# PWM_Controller_Half_Bridge.net
KiCad netlist of a schematic drawn in Altium Designer
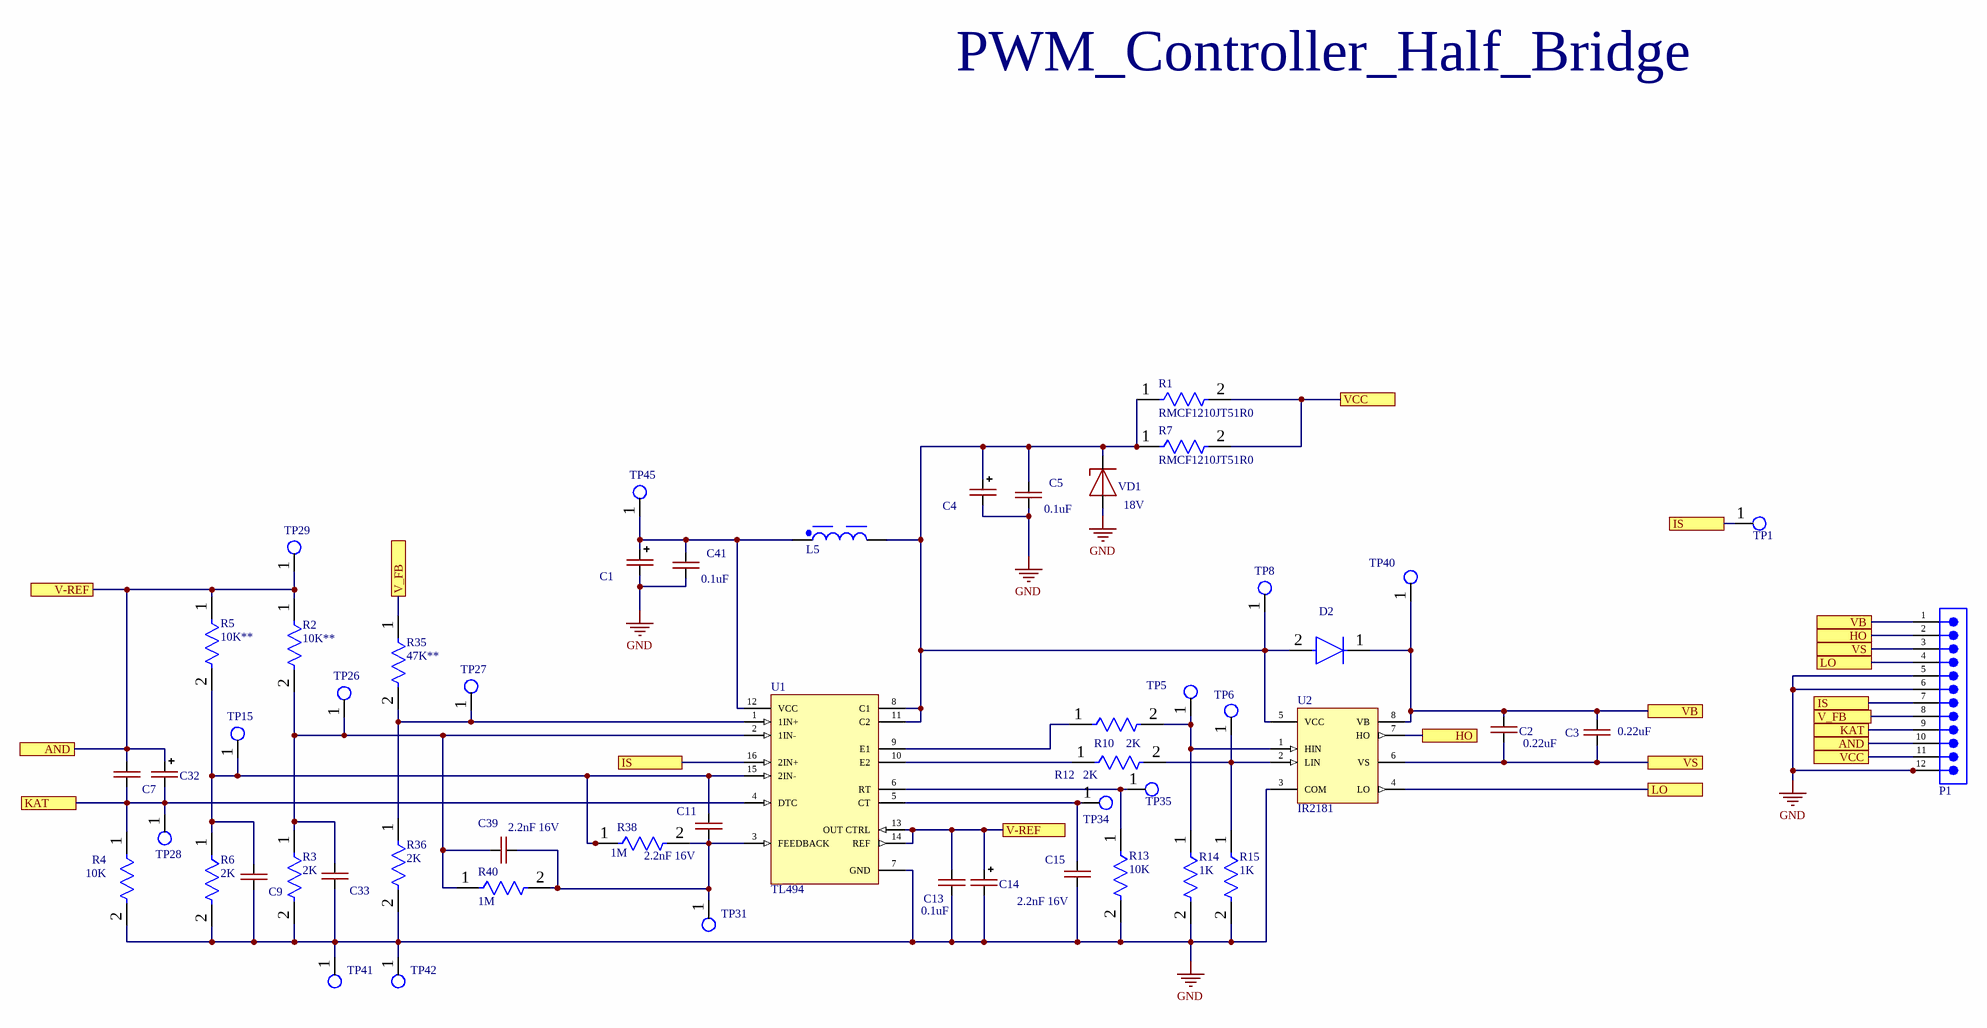
[diagram p0: PWM_Controller_Half_Bridge.SchDoc]

(export (version "E")
  (design (tool "Eeschema 10.0.6"))
  (components
    (comp (ref "C1")
      (value "CAP-POLAR")
      (footprint "SIZE_EEE")
      (libsource (lib "PASSIVE_COMPONENTS") (part "CAP-POLAR"))
    )
    (comp (ref "C2")
      (value "0.22uF")
      (footprint "FP-C1210X475K5RACTU-IPC_C")
      (libsource (lib "PASSIVE_COMPONENTS") (part "CAP_1210"))
    )
    (comp (ref "C3")
      (value "0.22uF")
      (footprint "FP-C1210X475K5RACTU-IPC_C")
      (libsource (lib "PASSIVE_COMPONENTS") (part "CAP_1210"))
    )
    (comp (ref "C4")
      (value "CAP-POLAR")
      (footprint "SIZE_EEE")
      (libsource (lib "PASSIVE_COMPONENTS") (part "CAP-POLAR"))
    )
    (comp (ref "C5")
      (value "0.1uF")
      (footprint "CAP-0805")
      (libsource (lib "PASSIVE_COMPONENTS") (part "CAP-NON-POLAR"))
    )
    (comp (ref "C7")
      (value "CAP-NON-POLAR")
      (footprint "CAP-0805")
      (libsource (lib "PASSIVE_COMPONENTS") (part "CAP-NON-POLAR"))
    )
    (comp (ref "C9")
      (value "CAP-NON-POLAR")
      (footprint "CAP-0805")
      (libsource (lib "PASSIVE_COMPONENTS") (part "CAP-NON-POLAR"))
    )
    (comp (ref "C11")
      (value "2.2nF 16V")
      (footprint "CAP-0805")
      (libsource (lib "PASSIVE_COMPONENTS") (part "CAP-NON-POLAR"))
    )
    (comp (ref "C13")
      (value "0.1uF")
      (footprint "CAP-0805")
      (libsource (lib "PASSIVE_COMPONENTS") (part "CAP-NON-POLAR"))
    )
    (comp (ref "C14")
      (value "CAP-POLAR")
      (footprint "SIZE_EEE")
      (libsource (lib "PASSIVE_COMPONENTS") (part "CAP-POLAR"))
    )
    (comp (ref "C15")
      (value "2.2nF 16V")
      (footprint "CAP-0805")
      (libsource (lib "PASSIVE_COMPONENTS") (part "CAP-NON-POLAR"))
    )
    (comp (ref "C32")
      (value "CAP-POLAR")
      (footprint "CAP-TAN-D")
      (libsource (lib "PASSIVE_COMPONENTS") (part "CAP-POLAR"))
    )
    (comp (ref "C33")
      (value "CAP-NON-POLAR")
      (footprint "CAP-0805")
      (libsource (lib "PASSIVE_COMPONENTS") (part "CAP-NON-POLAR"))
    )
    (comp (ref "C39")
      (value "2.2nF 16V")
      (footprint "CAP-0805")
      (libsource (lib "PASSIVE_COMPONENTS") (part "CAP-NON-POLAR"))
    )
    (comp (ref "C41")
      (value "0.1uF")
      (footprint "CAP-0805")
      (libsource (lib "PASSIVE_COMPONENTS") (part "CAP-NON-POLAR"))
    )
    (comp (ref "D2") (value "US1G") (footprint "DO-214AA") (libsource (lib "Diodes") (part "US1G")))
    (comp (ref "L5")
      (value "47µH, 1.17A")
      (footprint "WE-PD2_7850")
      (description "WE-PD2 SMT Power Inductor, size 7850, 47µH, 1.17A, 0.18Ω")
      (fields
        (field (name "MANUFACTURER PART NUMBER") "744775147")
        (field (name "MANUFACTURER") "Wurth Elektronik")
      )
      (libsource (lib "WE-PD2 (rev22d)") (part "744775147"))
    )
    (comp (ref "P1")
      (value "61301211021")
      (footprint "61301211021")
      (description "WR-PHD Pin Header, THT, Angled, pitch 2.54mm, 1 Row, 12P")
      (fields (field (name "MANUFACTURER") "Wurth Elektronik"))
      (libsource (lib "Altium_WR-PHD (rev22b)") (part "61301211021"))
    )
    (comp (ref "R1")
      (value "RMCF1210JT51R0")
      (footprint "FP-RMCF1210-MFG")
      (description "51Ω ±5% 0.5W 1210 Thick Film Chip Resistor AEC-Q200 compliant")
      (fields (field (name "TOLERANCE") "5%"))
      (libsource (lib "Altium Content Vault") (part "1029c3af85768c4190bb7ad29bc67b5"))
    )
    (comp (ref "R2")
      (value "10K**")
      (footprint "RES-0805")
      (description "10K")
      (libsource (lib "PASSIVE_COMPONENTS") (part "RES-CONST"))
    )
    (comp (ref "R3")
      (value "2K")
      (footprint "RES-0805")
      (libsource (lib "PASSIVE_COMPONENTS") (part "RES-CONST"))
    )
    (comp (ref "R4")
      (value "10K")
      (footprint "RES-0805")
      (libsource (lib "PASSIVE_COMPONENTS") (part "RES-CONST"))
    )
    (comp (ref "R5")
      (value "10K**")
      (footprint "RES-0805")
      (description "10K")
      (libsource (lib "PASSIVE_COMPONENTS") (part "RES-CONST"))
    )
    (comp (ref "R6")
      (value "2K")
      (footprint "RES-0805")
      (libsource (lib "PASSIVE_COMPONENTS") (part "RES-CONST"))
    )
    (comp (ref "R7")
      (value "RMCF1210JT51R0")
      (footprint "FP-RMCF1210-MFG")
      (description "51Ω ±5% 0.5W 1210 Thick Film Chip Resistor AEC-Q200 compliant")
      (fields (field (name "TOLERANCE") "5%"))
      (libsource (lib "Altium Content Vault") (part "1029c3af85768c4190bb7ad29bc67b5"))
    )
    (comp (ref "R10")
      (value "2K")
      (footprint "RES-0805")
      (libsource (lib "PASSIVE_COMPONENTS") (part "RES-CONST"))
    )
    (comp (ref "R12")
      (value "2K")
      (footprint "RES-0805")
      (libsource (lib "PASSIVE_COMPONENTS") (part "RES-CONST"))
    )
    (comp (ref "R13")
      (value "10K")
      (footprint "RES-0805")
      (libsource (lib "PASSIVE_COMPONENTS") (part "RES-CONST"))
    )
    (comp (ref "R14")
      (value "1K")
      (footprint "RES-0805")
      (libsource (lib "PASSIVE_COMPONENTS") (part "RES-CONST"))
    )
    (comp (ref "R15")
      (value "1K")
      (footprint "RES-0805")
      (libsource (lib "PASSIVE_COMPONENTS") (part "RES-CONST"))
    )
    (comp (ref "R35")
      (value "47K**")
      (footprint "RES-0805")
      (description "47K")
      (libsource (lib "PASSIVE_COMPONENTS") (part "RES-CONST"))
    )
    (comp (ref "R36")
      (value "2K")
      (footprint "RES-0805")
      (libsource (lib "PASSIVE_COMPONENTS") (part "RES-CONST"))
    )
    (comp (ref "R38")
      (value "1M")
      (footprint "RES-0805")
      (libsource (lib "PASSIVE_COMPONENTS") (part "RES-CONST"))
    )
    (comp (ref "R40")
      (value "1M")
      (footprint "RES-0805")
      (libsource (lib "PASSIVE_COMPONENTS") (part "RES-CONST"))
    )
    (comp (ref "TP1")
      (value "~")
      (footprint "Test_Point")
      (description "Test_Point")
      (libsource (lib "Connectors") (part "TP_PCB?"))
    )
    (comp (ref "TP5")
      (value "~")
      (footprint "Test_Point")
      (description "Test_Point")
      (libsource (lib "Connectors") (part "TP_PCB?"))
    )
    (comp (ref "TP6")
      (value "~")
      (footprint "Test_Point")
      (description "Test_Point")
      (libsource (lib "Connectors") (part "TP_PCB?"))
    )
    (comp (ref "TP8")
      (value "~")
      (footprint "Test_Point")
      (description "Test_Point")
      (libsource (lib "Connectors") (part "TP_PCB?"))
    )
    (comp (ref "TP15")
      (value "~")
      (footprint "Test_Point")
      (description "Test_Point")
      (libsource (lib "Connectors") (part "TP_PCB?"))
    )
    (comp (ref "TP26")
      (value "~")
      (footprint "Test_Point")
      (description "Test_Point")
      (libsource (lib "Connectors") (part "TP_PCB?"))
    )
    (comp (ref "TP27")
      (value "~")
      (footprint "Test_Point")
      (description "Test_Point")
      (libsource (lib "Connectors") (part "TP_PCB?"))
    )
    (comp (ref "TP28")
      (value "~")
      (footprint "Test_Point")
      (description "Test_Point")
      (libsource (lib "Connectors") (part "TP_PCB?"))
    )
    (comp (ref "TP29")
      (value "~")
      (footprint "Test_Point")
      (description "Test_Point")
      (libsource (lib "Connectors") (part "TP_PCB?"))
    )
    (comp (ref "TP31")
      (value "~")
      (footprint "Test_Point")
      (description "Test_Point")
      (libsource (lib "Connectors") (part "TP_PCB?"))
    )
    (comp (ref "TP34")
      (value "~")
      (footprint "Test_Point")
      (description "Test_Point")
      (libsource (lib "Connectors") (part "TP_PCB?"))
    )
    (comp (ref "TP35")
      (value "~")
      (footprint "Test_Point")
      (description "Test_Point")
      (libsource (lib "Connectors") (part "TP_PCB?"))
    )
    (comp (ref "TP40")
      (value "~")
      (footprint "Test_Point")
      (description "Test_Point")
      (libsource (lib "Connectors") (part "TP_PCB?"))
    )
    (comp (ref "TP41")
      (value "~")
      (footprint "Test_Point")
      (description "Test_Point")
      (libsource (lib "Connectors") (part "TP_PCB?"))
    )
    (comp (ref "TP42")
      (value "~")
      (footprint "Test_Point")
      (description "Test_Point")
      (libsource (lib "Connectors") (part "TP_PCB?"))
    )
    (comp (ref "TP45")
      (value "~")
      (footprint "Test_Point")
      (description "Test_Point")
      (libsource (lib "Connectors") (part "TP_PCB?"))
    )
    (comp (ref "U1")
      (value "TL494")
      (footprint "SOIC-16-M")
      (description "TL494 Pwm controller")
      (libsource (lib "Integrated_Circuts") (part "TL494"))
    )
    (comp (ref "U2")
      (value "IR2181")
      (footprint "SO8-150")
      (description "IR2181 Driver")
      (libsource (lib "Integrated_Circuts") (part "IR2181"))
    )
    (comp (ref "VD1") (value "18V") (footprint "DO-017AA") (libsource (lib "Diodes") (part "ZENER")))
  )
  (nets
    (net (code "1") (name "/AND") (class "Default")
      (node (ref "C13") (pin "2") (pinfunction "2_2") (pintype "passive"))
      (node (ref "C14") (pin "1") (pinfunction "+_1") (pintype "passive"))
      (node (ref "C32") (pin "1") (pinfunction "+_1") (pintype "passive"))
      (node (ref "C7") (pin "2") (pinfunction "2_2") (pintype "passive"))
      (node (ref "P1") (pin "10") (pinfunction "10_10") (pintype "passive"))
      (node (ref "R2") (pin "1") (pinfunction "1_1") (pintype "passive"))
      (node (ref "R5") (pin "1") (pinfunction "1_1") (pintype "passive"))
      (node (ref "TP29") (pin "1") (pinfunction "G9_1") (pintype "passive"))
      (node (ref "U1") (pin "13") (pinfunction "OUT_CTRL_13") (pintype "input"))
      (node (ref "U1") (pin "14") (pinfunction "REF_14") (pintype "output"))
    )
    (net (code "2") (name "/HO") (class "Default")
      (node (ref "P1") (pin "2") (pinfunction "2_2") (pintype "passive"))
      (node (ref "U2") (pin "7") (pinfunction "HO_7") (pintype "output"))
    )
    (net (code "3") (name "/IS") (class "Default")
      (node (ref "P1") (pin "7") (pinfunction "7_7") (pintype "passive"))
      (node (ref "TP1") (pin "1") (pinfunction "G9_1") (pintype "passive"))
      (node (ref "U1") (pin "16") (pinfunction "2IN+_16") (pintype "input"))
    )
    (net (code "4") (name "/KAT") (class "Default")
      (node (ref "C32") (pin "2") (pinfunction "-_2") (pintype "passive"))
      (node (ref "C7") (pin "1") (pinfunction "1_1") (pintype "passive"))
      (node (ref "P1") (pin "9") (pinfunction "9_9") (pintype "passive"))
      (node (ref "R4") (pin "1") (pinfunction "1_1") (pintype "passive"))
      (node (ref "TP28") (pin "1") (pinfunction "G9_1") (pintype "passive"))
      (node (ref "U1") (pin "4") (pinfunction "DTC_4") (pintype "input"))
    )
    (net (code "5") (name "/LO") (class "Default")
      (node (ref "P1") (pin "4") (pinfunction "4_4") (pintype "passive"))
      (node (ref "U2") (pin "4") (pinfunction "LO_4") (pintype "output"))
    )
    (net (code "6") (name "/VB") (class "Default")
      (node (ref "C2") (pin "2") (pinfunction "2_2") (pintype "passive"))
      (node (ref "C3") (pin "2") (pinfunction "2_2") (pintype "passive"))
      (node (ref "D2") (pin "1") (pinfunction "C_1") (pintype "passive"))
      (node (ref "P1") (pin "1") (pinfunction "1_1") (pintype "passive"))
      (node (ref "TP40") (pin "1") (pinfunction "G9_1") (pintype "passive"))
      (node (ref "U2") (pin "8") (pinfunction "VB_8") (pintype "power_in"))
    )
    (net (code "7") (name "/VCC") (class "Default")
      (node (ref "P1") (pin "11") (pinfunction "11_11") (pintype "passive"))
      (node (ref "R1") (pin "2") (pinfunction "2_2") (pintype "passive"))
      (node (ref "R7") (pin "2") (pinfunction "2_2") (pintype "passive"))
    )
    (net (code "8") (name "/VS") (class "Default")
      (node (ref "C2") (pin "1") (pinfunction "1_1") (pintype "passive"))
      (node (ref "C3") (pin "1") (pinfunction "1_1") (pintype "passive"))
      (node (ref "P1") (pin "3") (pinfunction "3_3") (pintype "passive"))
      (node (ref "U2") (pin "6") (pinfunction "VS_6") (pintype "power_in"))
    )
    (net (code "9") (name "/V_FB") (class "Default")
      (node (ref "P1") (pin "8") (pinfunction "8_8") (pintype "passive"))
      (node (ref "R35") (pin "1") (pinfunction "1_1") (pintype "passive"))
    )
    (net (code "10") (name "GND") (class "Default")
      (node (ref "C1") (pin "2") (pinfunction "-_2") (pintype "passive"))
      (node (ref "C13") (pin "1") (pinfunction "1_1") (pintype "passive"))
      (node (ref "C14") (pin "2") (pinfunction "-_2") (pintype "passive"))
      (node (ref "C15") (pin "1") (pinfunction "1_1") (pintype "passive"))
      (node (ref "C33") (pin "1") (pinfunction "1_1") (pintype "passive"))
      (node (ref "C4") (pin "2") (pinfunction "-_2") (pintype "passive"))
      (node (ref "C41") (pin "1") (pinfunction "1_1") (pintype "passive"))
      (node (ref "C5") (pin "1") (pinfunction "1_1") (pintype "passive"))
      (node (ref "C9") (pin "1") (pinfunction "1_1") (pintype "passive"))
      (node (ref "P1") (pin "12") (pinfunction "12_12") (pintype "passive"))
      (node (ref "P1") (pin "5") (pinfunction "5_5") (pintype "passive"))
      (node (ref "P1") (pin "6") (pinfunction "6_6") (pintype "passive"))
      (node (ref "R13") (pin "2") (pinfunction "2_2") (pintype "passive"))
      (node (ref "R14") (pin "2") (pinfunction "2_2") (pintype "passive"))
      (node (ref "R15") (pin "2") (pinfunction "2_2") (pintype "passive"))
      (node (ref "R3") (pin "2") (pinfunction "2_2") (pintype "passive"))
      (node (ref "R36") (pin "2") (pinfunction "2_2") (pintype "passive"))
      (node (ref "R4") (pin "2") (pinfunction "2_2") (pintype "passive"))
      (node (ref "R6") (pin "2") (pinfunction "2_2") (pintype "passive"))
      (node (ref "TP41") (pin "1") (pinfunction "G9_1") (pintype "passive"))
      (node (ref "TP42") (pin "1") (pinfunction "G9_1") (pintype "passive"))
      (node (ref "U1") (pin "7") (pinfunction "GND_7") (pintype "power_in"))
      (node (ref "U2") (pin "3") (pinfunction "COM_3") (pintype "passive"))
      (node (ref "VD1") (pin "2") (pinfunction "A_2") (pintype "passive"))
    )
    (net (code "11") (name "Net-(C1-+)") (class "Default")
      (node (ref "C1") (pin "1") (pinfunction "+_1") (pintype "passive"))
      (node (ref "C41") (pin "2") (pinfunction "2_2") (pintype "passive"))
      (node (ref "L5") (pin "1") (pinfunction "1_1") (pintype "passive"))
      (node (ref "TP45") (pin "1") (pinfunction "G9_1") (pintype "passive"))
      (node (ref "U1") (pin "12") (pinfunction "VCC_12") (pintype "power_in"))
    )
    (net (code "12") (name "Net-(C4-+)") (class "Default")
      (node (ref "C4") (pin "1") (pinfunction "+_1") (pintype "passive"))
      (node (ref "C5") (pin "2") (pinfunction "2_2") (pintype "passive"))
      (node (ref "D2") (pin "2") (pinfunction "A_2") (pintype "passive"))
      (node (ref "L5") (pin "2") (pinfunction "2_2") (pintype "passive"))
      (node (ref "R1") (pin "1") (pinfunction "1_1") (pintype "passive"))
      (node (ref "R7") (pin "1") (pinfunction "1_1") (pintype "passive"))
      (node (ref "TP8") (pin "1") (pinfunction "G9_1") (pintype "passive"))
      (node (ref "U1") (pin "11") (pinfunction "C2_11") (pintype "passive"))
      (node (ref "U1") (pin "8") (pinfunction "C1_8") (pintype "passive"))
      (node (ref "U2") (pin "5") (pinfunction "VCC_5") (pintype "power_in"))
      (node (ref "VD1") (pin "1") (pinfunction "C_1") (pintype "passive"))
    )
    (net (code "13") (name "Net-(TP5-G9)") (class "Default")
      (node (ref "R10") (pin "2") (pinfunction "2_2") (pintype "passive"))
      (node (ref "R14") (pin "1") (pinfunction "1_1") (pintype "passive"))
      (node (ref "TP5") (pin "1") (pinfunction "G9_1") (pintype "passive"))
      (node (ref "U2") (pin "1") (pinfunction "HIN_1") (pintype "input"))
    )
    (net (code "14") (name "Net-(TP6-G9)") (class "Default")
      (node (ref "R12") (pin "2") (pinfunction "2_2") (pintype "passive"))
      (node (ref "R15") (pin "1") (pinfunction "1_1") (pintype "passive"))
      (node (ref "TP6") (pin "1") (pinfunction "G9_1") (pintype "passive"))
      (node (ref "U2") (pin "2") (pinfunction "LIN_2") (pintype "input"))
    )
    (net (code "15") (name "Net-(TP15-G9)") (class "Default")
      (node (ref "C11") (pin "2") (pinfunction "2_2") (pintype "passive"))
      (node (ref "C9") (pin "2") (pinfunction "2_2") (pintype "passive"))
      (node (ref "R38") (pin "1") (pinfunction "1_1") (pintype "passive"))
      (node (ref "R5") (pin "2") (pinfunction "2_2") (pintype "passive"))
      (node (ref "R6") (pin "1") (pinfunction "1_1") (pintype "passive"))
      (node (ref "TP15") (pin "1") (pinfunction "G9_1") (pintype "passive"))
      (node (ref "U1") (pin "15") (pinfunction "2IN-_15") (pintype "input"))
    )
    (net (code "16") (name "Net-(TP26-G9)") (class "Default")
      (node (ref "C33") (pin "2") (pinfunction "2_2") (pintype "passive"))
      (node (ref "C39") (pin "2") (pinfunction "2_2") (pintype "passive"))
      (node (ref "R2") (pin "2") (pinfunction "2_2") (pintype "passive"))
      (node (ref "R3") (pin "1") (pinfunction "1_1") (pintype "passive"))
      (node (ref "R40") (pin "1") (pinfunction "1_1") (pintype "passive"))
      (node (ref "TP26") (pin "1") (pinfunction "G9_1") (pintype "passive"))
      (node (ref "U1") (pin "2") (pinfunction "1IN-_2") (pintype "input"))
    )
    (net (code "17") (name "Net-(TP27-G9)") (class "Default")
      (node (ref "R35") (pin "2") (pinfunction "2_2") (pintype "passive"))
      (node (ref "R36") (pin "1") (pinfunction "1_1") (pintype "passive"))
      (node (ref "TP27") (pin "1") (pinfunction "G9_1") (pintype "passive"))
      (node (ref "U1") (pin "1") (pinfunction "1IN+_1") (pintype "input"))
    )
    (net (code "18") (name "Net-(TP31-G9)") (class "Default")
      (node (ref "C11") (pin "1") (pinfunction "1_1") (pintype "passive"))
      (node (ref "C39") (pin "1") (pinfunction "1_1") (pintype "passive"))
      (node (ref "R38") (pin "2") (pinfunction "2_2") (pintype "passive"))
      (node (ref "R40") (pin "2") (pinfunction "2_2") (pintype "passive"))
      (node (ref "TP31") (pin "1") (pinfunction "G9_1") (pintype "passive"))
      (node (ref "U1") (pin "3") (pinfunction "FEEDBACK_3") (pintype "input"))
    )
    (net (code "19") (name "Net-(TP34-G9)") (class "Default")
      (node (ref "C15") (pin "2") (pinfunction "2_2") (pintype "passive"))
      (node (ref "TP34") (pin "1") (pinfunction "G9_1") (pintype "passive"))
      (node (ref "U1") (pin "5") (pinfunction "CT_5") (pintype "passive"))
    )
    (net (code "20") (name "Net-(TP35-G9)") (class "Default")
      (node (ref "R13") (pin "1") (pinfunction "1_1") (pintype "passive"))
      (node (ref "TP35") (pin "1") (pinfunction "G9_1") (pintype "passive"))
      (node (ref "U1") (pin "6") (pinfunction "RT_6") (pintype "passive"))
    )
    (net (code "21") (name "Net-(U1-E1)") (class "Default")
      (node (ref "R10") (pin "1") (pinfunction "1_1") (pintype "passive"))
      (node (ref "U1") (pin "9") (pinfunction "E1_9") (pintype "passive"))
    )
    (net (code "22") (name "Net-(U1-E2)") (class "Default")
      (node (ref "R12") (pin "1") (pinfunction "1_1") (pintype "passive"))
      (node (ref "U1") (pin "10") (pinfunction "E2_10") (pintype "passive"))
    )
  )
)
